# NTP_Clock_stm32f107.net
KiCad netlist of a schematic drawn in Altium Designer
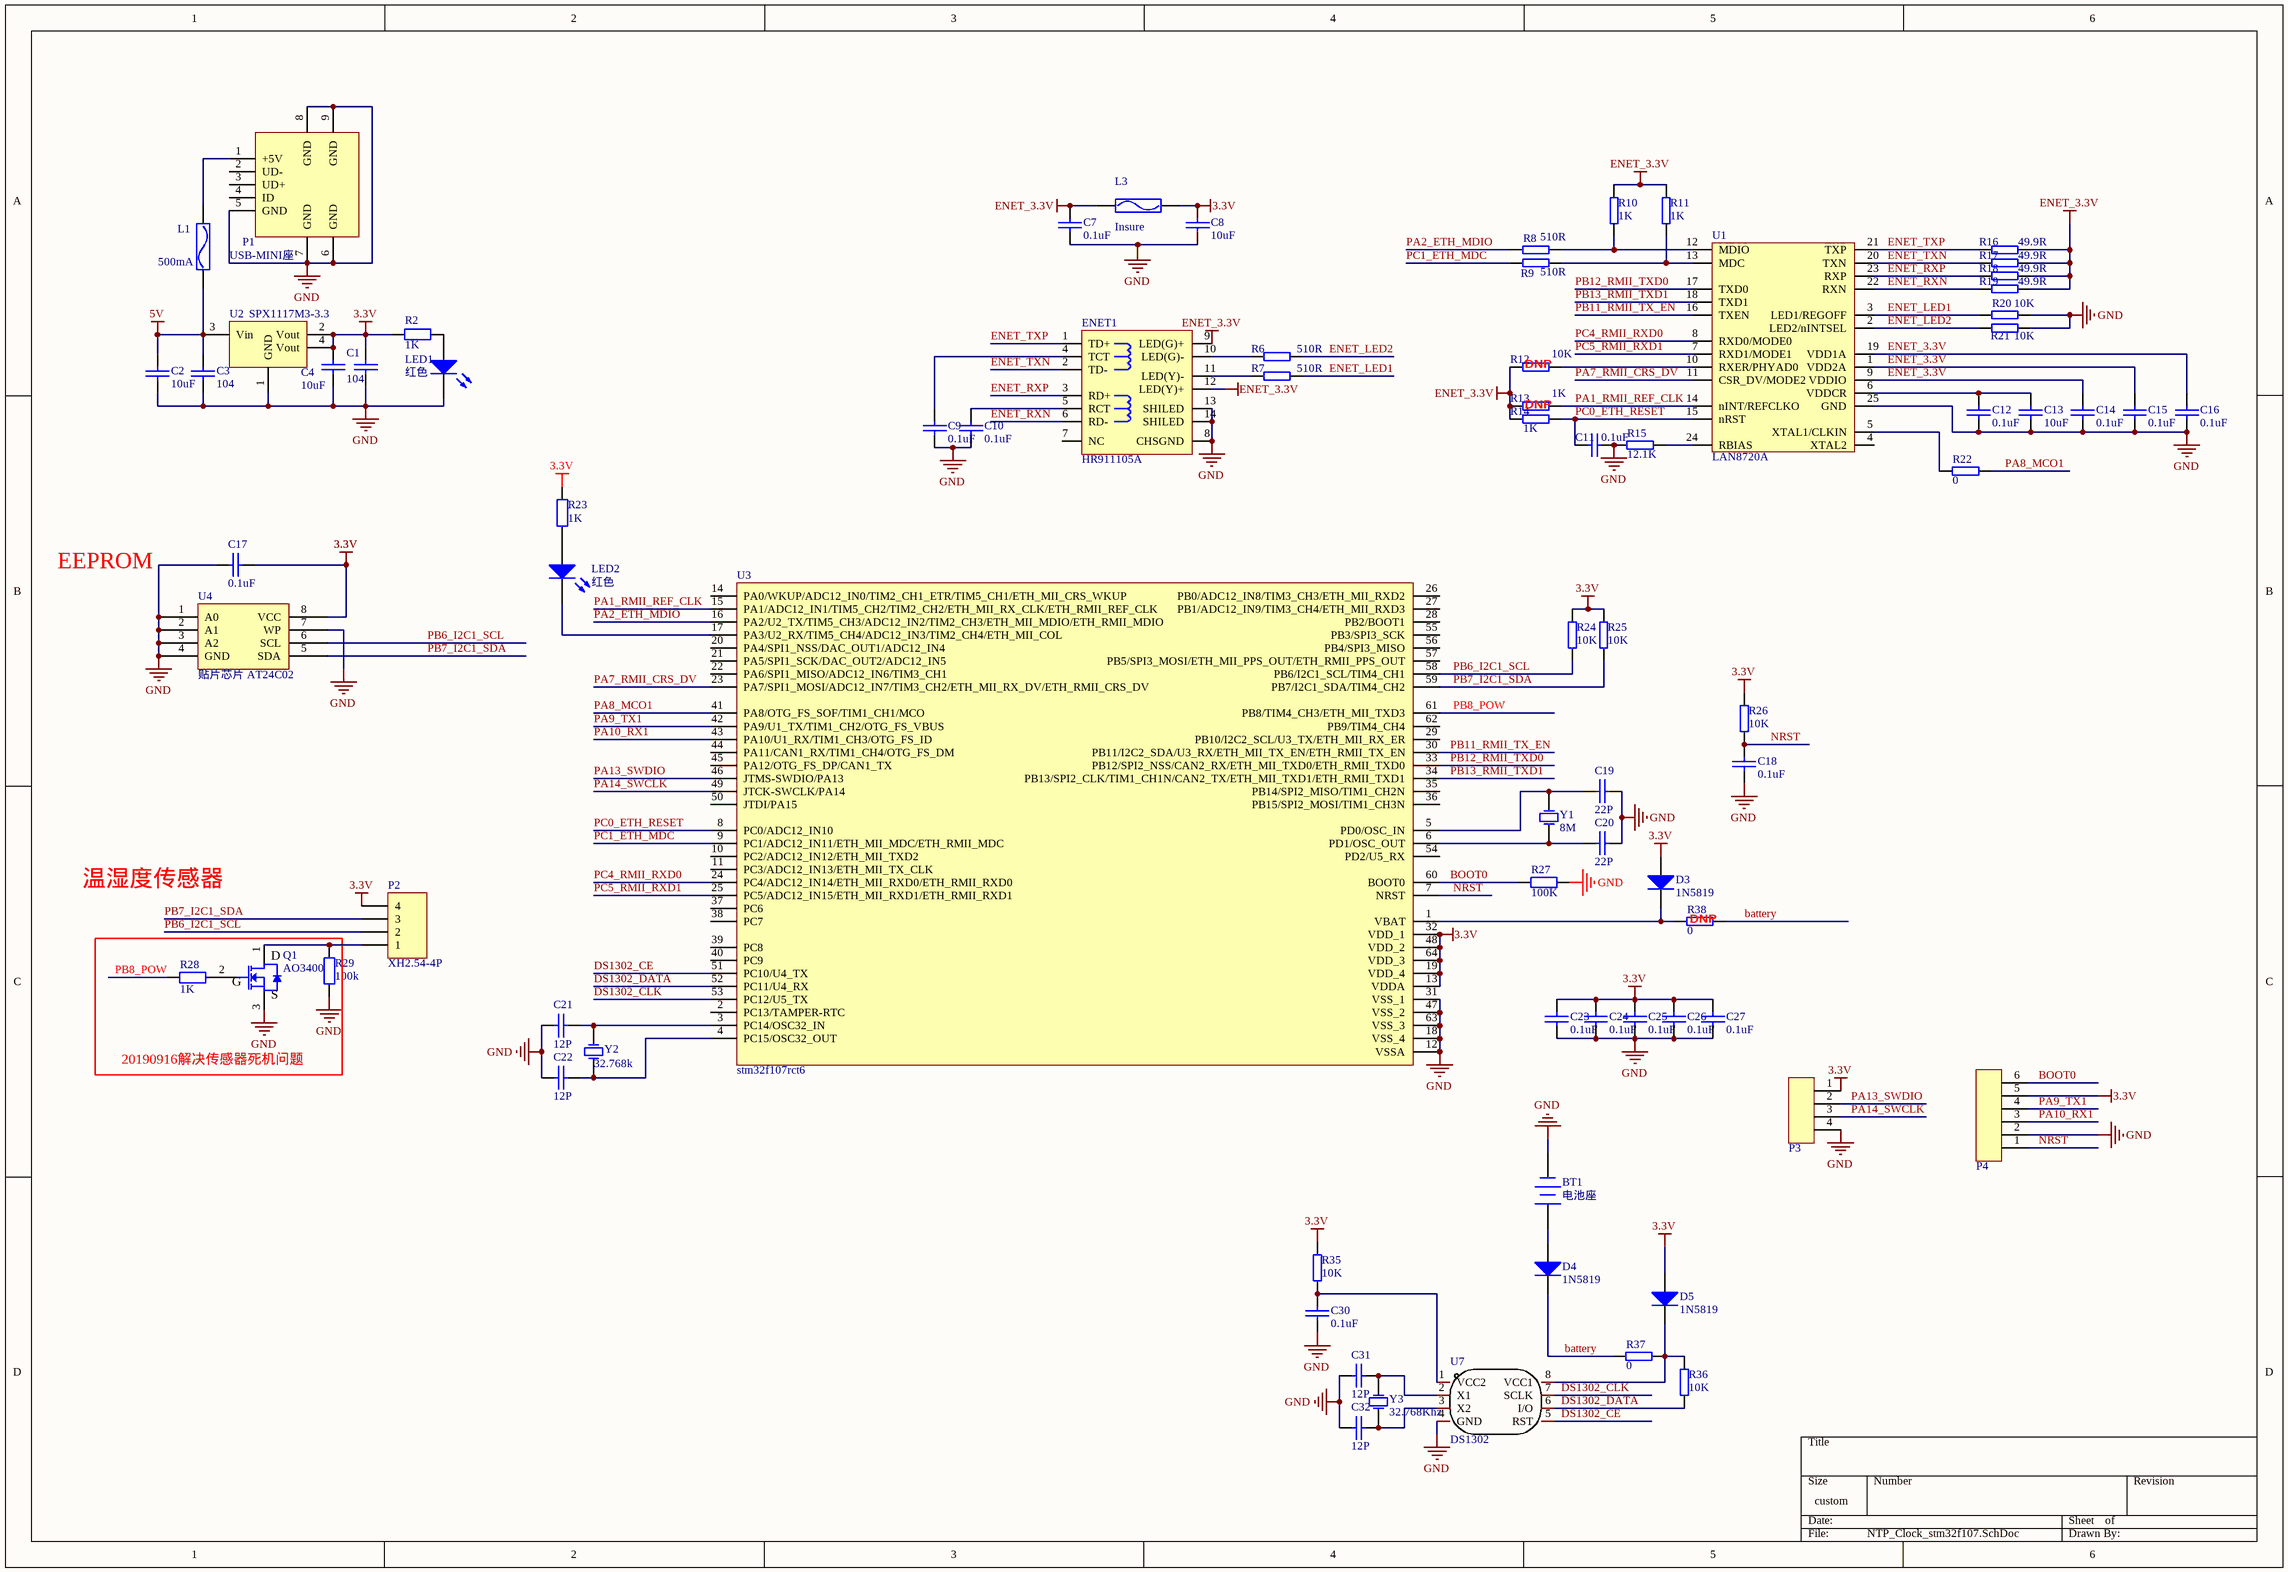
[diagram p0: NTP_Clock_stm32f107.SchDoc]

(export (version "E")
  (design (tool "Eeschema 10.0.6"))
  (components
    (comp (ref "BT1")
      (value "电池座")
      (footprint "BAT-3V")
      (fields (field (name "PUBLISHER") "Altium Limited"))
      (libsource (lib "Sch_Device_veryaz") (part "电池座"))
    )
    (comp (ref "C1")
      (value "104")
      (footprint "0805")
      (libsource (lib "Sch_Device_Simple") (part "贴片电容 0805"))
    )
    (comp (ref "C2")
      (value "10uF")
      (footprint "1206")
      (libsource (lib "Sch_Device_Simple") (part "贴片电容 0805"))
    )
    (comp (ref "C3")
      (value "104")
      (footprint "0805")
      (libsource (lib "Sch_Device_Simple") (part "贴片电容 0805"))
    )
    (comp (ref "C4")
      (value "10uF")
      (footprint "1206")
      (libsource (lib "Sch_Device_Simple") (part "贴片电容 0805"))
    )
    (comp (ref "C7") (value "0.1uF") (footprint "0805") (libsource (lib "Sch_Device_veryaz") (part "电容 贴片")))
    (comp (ref "C8") (value "10uF") (footprint "1206") (libsource (lib "Sch_Device_veryaz") (part "电容 贴片")))
    (comp (ref "C9") (value "0.1uF") (footprint "0805") (libsource (lib "Sch_Device_veryaz") (part "电容 贴片")))
    (comp (ref "C10") (value "0.1uF") (footprint "0805") (libsource (lib "Sch_Device_veryaz") (part "电容 贴片")))
    (comp (ref "C11") (value "0.1uF") (footprint "0805") (libsource (lib "Sch_Device_veryaz") (part "电容 贴片")))
    (comp (ref "C12") (value "0.1uF") (footprint "0805") (libsource (lib "Sch_Device_veryaz") (part "电容 贴片")))
    (comp (ref "C13") (value "10uF") (footprint "1206") (libsource (lib "Sch_Device_veryaz") (part "电容 贴片")))
    (comp (ref "C14") (value "0.1uF") (footprint "0805") (libsource (lib "Sch_Device_veryaz") (part "电容 贴片")))
    (comp (ref "C15") (value "0.1uF") (footprint "0805") (libsource (lib "Sch_Device_veryaz") (part "电容 贴片")))
    (comp (ref "C16") (value "0.1uF") (footprint "0805") (libsource (lib "Sch_Device_veryaz") (part "电容 贴片")))
    (comp (ref "C17") (value "0.1uF") (footprint "0805") (libsource (lib "Sch_Device_veryaz") (part "电容 贴片")))
    (comp (ref "C18") (value "0.1uF") (footprint "0805") (libsource (lib "Sch_Device_veryaz") (part "电容 贴片")))
    (comp (ref "C19") (value "22P") (footprint "0805") (libsource (lib "Sch_Device_veryaz") (part "电容 贴片")))
    (comp (ref "C20") (value "22P") (footprint "0805") (libsource (lib "Sch_Device_veryaz") (part "电容 贴片")))
    (comp (ref "C21") (value "12P") (footprint "0805") (libsource (lib "Sch_Device_veryaz") (part "电容 贴片")))
    (comp (ref "C22") (value "12P") (footprint "0805") (libsource (lib "Sch_Device_veryaz") (part "电容 贴片")))
    (comp (ref "C23") (value "0.1uF") (footprint "0805") (libsource (lib "Sch_Device_veryaz") (part "电容 贴片")))
    (comp (ref "C24") (value "0.1uF") (footprint "0805") (libsource (lib "Sch_Device_veryaz") (part "电容 贴片")))
    (comp (ref "C25") (value "0.1uF") (footprint "0805") (libsource (lib "Sch_Device_veryaz") (part "电容 贴片")))
    (comp (ref "C26") (value "0.1uF") (footprint "0805") (libsource (lib "Sch_Device_veryaz") (part "电容 贴片")))
    (comp (ref "C27") (value "0.1uF") (footprint "0805") (libsource (lib "Sch_Device_veryaz") (part "电容 贴片")))
    (comp (ref "C30") (value "0.1uF") (footprint "0805") (libsource (lib "Sch_Device_veryaz") (part "电容 贴片")))
    (comp (ref "C31") (value "12P") (footprint "0805") (libsource (lib "Sch_Device_veryaz") (part "电容 贴片")))
    (comp (ref "C32") (value "12P") (footprint "0805") (libsource (lib "Sch_Device_veryaz") (part "电容 贴片")))
    (comp (ref "D3")
      (value "1N5819")
      (footprint "二极管 贴片 IN4148")
      (libsource (lib "Sch_Device_veryaz") (part "二极管 贴片 1N4148"))
    )
    (comp (ref "D4")
      (value "1N5819")
      (footprint "二极管 贴片 IN4148")
      (libsource (lib "Sch_Device_veryaz") (part "二极管 贴片 1N4148"))
    )
    (comp (ref "D5")
      (value "1N5819")
      (footprint "二极管 贴片 IN4148")
      (libsource (lib "Sch_Device_veryaz") (part "二极管 贴片 1N4148"))
    )
    (comp (ref "ENET1")
      (value "HR911105A")
      (footprint "RJ-45A12")
      (description "带灯以太网接口")
      (fields (field (name "版权归属") "源创客"))
      (libsource (lib "IMX6UL_ALPHA(底板)_V2.0") (part "HR911105A"))
    )
    (comp (ref "L1") (value "500mA") (footprint "0805") (libsource (lib "Sch_Device_veryaz") (part "保险_自恢复")))
    (comp (ref "L3")
      (value "Insure")
      (footprint "0805")
      (libsource (lib "Sch_Device_veryaz") (part "保险 自恢复"))
    )
    (comp (ref "LED1")
      (value "红色")
      (footprint "LED5_单色")
      (description "D_RED_D")
      (libsource (lib "Sch_Device_Simple") (part "发光二极管 Φ3"))
    )
    (comp (ref "LED2")
      (value "红色")
      (footprint "LED5_单色")
      (description "D_RED_D")
      (libsource (lib "Sch_Device_Simple") (part "发光二极管 Φ3"))
    )
    (comp (ref "P1")
      (value "USB-MINI座")
      (footprint "USB MINI DIP")
      (libsource (lib "Sch_Device_veryaz") (part "联结件 USB-MINI座"))
    )
    (comp (ref "P2")
      (value "XH2.54-4P")
      (footprint "CONN-SMD_HCZZ0021-4")
      (libsource (lib "Sch_Device_veryaz") (part "联结件 XH2.54-4"))
    )
    (comp (ref "P3")
      (value "2.54 1*4")
      (footprint "单排插针 2.54 1*4")
      (libsource (lib "Sch_Device_veryaz") (part "连接件 单排插针 2.54 1*4"))
    )
    (comp (ref "P4")
      (value "2.54 1*6")
      (footprint "CONN-SMD_6P-P2.50_BX-HA2.54-6PWT")
      (libsource (lib "Sch_Device_veryaz") (part "连接件 单排插针 2.54 1*6"))
    )
    (comp (ref "Q1")
      (value "AO3400")
      (footprint "sot23d")
      (libsource (lib "Sch_Device_veryaz") (part "MOS管 AO3400"))
    )
    (comp (ref "R2") (value "1K") (footprint "0805") (libsource (lib "Sch_Device_Simple") (part "贴片电阻 0805")))
    (comp (ref "R6") (value "510R") (footprint "0805") (libsource (lib "") (part "电阻 贴片_1")))
    (comp (ref "R7") (value "510R") (footprint "0805") (libsource (lib "") (part "电阻 贴片_1")))
    (comp (ref "R8") (value "510R") (footprint "0805") (libsource (lib "") (part "电阻 贴片_1")))
    (comp (ref "R9") (value "510R") (footprint "0805") (libsource (lib "") (part "电阻 贴片_1")))
    (comp (ref "R10") (value "1K") (footprint "0805") (libsource (lib "Sch_Device_veryaz") (part "电阻 贴片")))
    (comp (ref "R11") (value "1K") (footprint "0805") (libsource (lib "Sch_Device_veryaz") (part "电阻 贴片")))
    (comp (ref "R12") (value "10K") (footprint "0805") (libsource (lib "") (part "电阻 贴片_1")))
    (comp (ref "R13") (value "1K") (footprint "0805") (libsource (lib "") (part "电阻 贴片_1")))
    (comp (ref "R14") (value "1K") (footprint "0805") (libsource (lib "") (part "电阻 贴片_1")))
    (comp (ref "R15") (value "12.1K") (footprint "0805") (libsource (lib "") (part "电阻 贴片_1")))
    (comp (ref "R16") (value "49.9R") (footprint "0805") (libsource (lib "") (part "电阻 贴片_1")))
    (comp (ref "R17") (value "49.9R") (footprint "0805") (libsource (lib "") (part "电阻 贴片_1")))
    (comp (ref "R18") (value "49.9R") (footprint "0805") (libsource (lib "") (part "电阻 贴片_1")))
    (comp (ref "R19") (value "49.9R") (footprint "0805") (libsource (lib "") (part "电阻 贴片_1")))
    (comp (ref "R20") (value "10K") (footprint "0805") (libsource (lib "") (part "电阻 贴片_1")))
    (comp (ref "R21") (value "10K") (footprint "0805") (libsource (lib "") (part "电阻 贴片_1")))
    (comp (ref "R22") (value "0") (footprint "0805") (libsource (lib "") (part "电阻 贴片_1")))
    (comp (ref "R23") (value "1K") (footprint "0805") (libsource (lib "") (part "贴片电阻 0805_1")))
    (comp (ref "R24") (value "10K") (footprint "0805") (libsource (lib "Sch_Device_veryaz") (part "电阻 贴片")))
    (comp (ref "R25") (value "10K") (footprint "0805") (libsource (lib "Sch_Device_veryaz") (part "电阻 贴片")))
    (comp (ref "R26") (value "10K") (footprint "0805") (libsource (lib "") (part "电阻 贴片_2")))
    (comp (ref "R27")
      (value "100K")
      (footprint "0805")
      (libsource (lib "Sch_Device_Simple") (part "贴片电阻 0805"))
    )
    (comp (ref "R28") (value "1K") (footprint "0805") (libsource (lib "") (part "贴片电阻 0603_1")))
    (comp (ref "R29")
      (value "100k")
      (footprint "0805")
      (libsource (lib "Sch_Device_veryaz") (part "贴片电阻 0603"))
    )
    (comp (ref "R35") (value "10K") (footprint "0805") (libsource (lib "") (part "电阻 贴片_2")))
    (comp (ref "R36") (value "10K") (footprint "0805") (libsource (lib "Sch_Device_veryaz") (part "电阻 贴片")))
    (comp (ref "R37") (value "0") (footprint "0805") (libsource (lib "") (part "电阻 贴片_1")))
    (comp (ref "R38") (value "0") (footprint "0805") (libsource (lib "") (part "电阻 贴片_1")))
    (comp (ref "U1")
      (value "LAN8720A")
      (footprint "QFN24")
      (description "ETH PHY")
      (libsource (lib "IMX6UL_ALPHA(底板)_V2.0") (part "LAN8720"))
    )
    (comp (ref "U2")
      (value "SPX1117M3-3.3")
      (footprint "SOT223")
      (libsource (lib "Sch_Device_veryaz") (part "贴片芯片 SPX1117M3-5.0"))
    )
    (comp (ref "U3")
      (value "stm32f107rct6")
      (footprint "stm32f107rct6")
      (libsource (lib "MyLib") (part "stm32f107rct6"))
    )
    (comp (ref "U4")
      (value "贴片芯片 AT24C02")
      (footprint "SOIC8")
      (libsource (lib "Sch_Device_veryaz") (part "贴片芯片 AT24C02"))
    )
    (comp (ref "U7")
      (value "DS1302")
      (footprint "SOP-8_L4.9-W3.9-P1.27-LS6.0-BL")
      (description "工业级 具有涓细电流充电能力的低功耗实时时钟芯片")
      (fields
        (field (name "MANUFACTURER") "HGSEMI(华冠)")
        (field (name "MANUFACTURER PART") "DS1302ZM")
        (field (name "NAME") "DS1302")
      )
      (libsource (lib "Sch_Device_veryaz") (part "DS1302"))
    )
    (comp (ref "Y1")
      (value "8M")
      (footprint "晶振 BCY-W2/E4.7_贴")
      (libsource (lib "Sch_Device_veryaz") (part "晶振 直插矮"))
    )
    (comp (ref "Y2") (value "32.768k") (footprint "晶振 卧 8*2mm") (libsource (lib "") (part "晶振 直插矮_1")))
    (comp (ref "Y3")
      (value "32.768Khz")
      (footprint "晶振 卧 8*2mm")
      (libsource (lib "Sch_Device_veryaz") (part "晶振 直插"))
    )
  )
  (nets
    (net (code "1") (name "/BOOT0") (class "Default")
      (node (ref "P4") (pin "6") (pinfunction "6_6") (pintype "passive"))
      (node (ref "R27") (pin "2") (pinfunction "2_2") (pintype "passive"))
      (node (ref "U3") (pin "60") (pinfunction "BOOT0_60") (pintype "passive"))
    )
    (net (code "2") (name "/DS1302_CE") (class "Default")
      (node (ref "U3") (pin "51") (pinfunction "PC10/U4_TX_51") (pintype "passive"))
      (node (ref "U7") (pin "5") (pinfunction "RST_5") (pintype "passive"))
    )
    (net (code "3") (name "/DS1302_CLK") (class "Default")
      (node (ref "U3") (pin "53") (pinfunction "PC12/U5_TX_53") (pintype "passive"))
      (node (ref "U7") (pin "7") (pinfunction "SCLK_7") (pintype "passive"))
    )
    (net (code "4") (name "/DS1302_DATA") (class "Default")
      (node (ref "R36") (pin "2") (pinfunction "2_2") (pintype "passive"))
      (node (ref "U3") (pin "52") (pinfunction "PC11/U4_RX_52") (pintype "passive"))
      (node (ref "U7") (pin "6") (pinfunction "I/O_6") (pintype "passive"))
    )
    (net (code "5") (name "/ENET_LED1") (class "Default")
      (node (ref "R20") (pin "2") (pinfunction "2_2") (pintype "passive"))
      (node (ref "R7") (pin "1") (pinfunction "1_1") (pintype "passive"))
      (node (ref "U1") (pin "3") (pinfunction "LED1/REGOFF_3") (pintype "passive"))
    )
    (net (code "6") (name "/ENET_LED2") (class "Default")
      (node (ref "R21") (pin "2") (pinfunction "2_2") (pintype "passive"))
      (node (ref "R6") (pin "1") (pinfunction "1_1") (pintype "passive"))
      (node (ref "U1") (pin "2") (pinfunction "LED2/nINTSEL_2") (pintype "passive"))
    )
    (net (code "7") (name "/ENET_RXN") (class "Default")
      (node (ref "ENET1") (pin "6") (pinfunction "RD-_6") (pintype "passive"))
      (node (ref "R19") (pin "2") (pinfunction "2_2") (pintype "passive"))
      (node (ref "U1") (pin "22") (pinfunction "RXN_22") (pintype "passive"))
    )
    (net (code "8") (name "/ENET_RXP") (class "Default")
      (node (ref "ENET1") (pin "3") (pinfunction "RD+_3") (pintype "passive"))
      (node (ref "R18") (pin "2") (pinfunction "2_2") (pintype "passive"))
      (node (ref "U1") (pin "23") (pinfunction "RXP_23") (pintype "passive"))
    )
    (net (code "9") (name "/ENET_TXN") (class "Default")
      (node (ref "ENET1") (pin "2") (pinfunction "TD-_2") (pintype "passive"))
      (node (ref "R17") (pin "2") (pinfunction "2_2") (pintype "passive"))
      (node (ref "U1") (pin "20") (pinfunction "TXN_20") (pintype "passive"))
    )
    (net (code "10") (name "/ENET_TXP") (class "Default")
      (node (ref "ENET1") (pin "1") (pinfunction "TD+_1") (pintype "passive"))
      (node (ref "R16") (pin "2") (pinfunction "2_2") (pintype "passive"))
      (node (ref "U1") (pin "21") (pinfunction "TXP_21") (pintype "passive"))
    )
    (net (code "11") (name "/NRST") (class "Default")
      (node (ref "C18") (pin "1") (pintype "passive"))
      (node (ref "P4") (pin "1") (pinfunction "1_1") (pintype "passive"))
      (node (ref "R26") (pin "1") (pinfunction "1_1") (pintype "passive"))
      (node (ref "U3") (pin "7") (pinfunction "NRST_7") (pintype "passive"))
    )
    (net (code "12") (name "/PA1_RMII_REF_CLK") (class "Default")
      (node (ref "R13") (pin "1") (pinfunction "1_1") (pintype "passive"))
      (node (ref "U1") (pin "14") (pinfunction "nINT/REFCLKO_14") (pintype "passive"))
      (node (ref "U3") (pin "15") (pinfunction "PA1/ADC12_IN1/TIM5_CH2/TIM2_CH2/ETH_MII_RX_CLK/ETH_RMII_REF_CLK_15") (pintype "passive"))
    )
    (net (code "13") (name "/PA2_ETH_MDIO") (class "Default")
      (node (ref "R8") (pin "2") (pinfunction "2_2") (pintype "passive"))
      (node (ref "U3") (pin "16") (pinfunction "PA2/U2_TX/TIM5_CH3/ADC12_IN2/TIM2_CH3/ETH_MII_MDIO/ETH_RMII_MDIO_16") (pintype "passive"))
    )
    (net (code "14") (name "/PA7_RMII_CRS_DV") (class "Default")
      (node (ref "U1") (pin "11") (pinfunction "CSR_DV/MODE2_11") (pintype "passive"))
      (node (ref "U3") (pin "23") (pinfunction "PA7/SPI1_MOSI/ADC12_IN7/TIM3_CH2/ETH_MII_RX_DV/ETH_RMII_CRS_DV_23") (pintype "passive"))
    )
    (net (code "15") (name "/PA8_MCO1") (class "Default")
      (node (ref "R22") (pin "1") (pinfunction "1_1") (pintype "passive"))
      (node (ref "U3") (pin "41") (pinfunction "PA8/OTG_FS_SOF/TIM1_CH1/MCO_41") (pintype "passive"))
    )
    (net (code "16") (name "/PA9_TX1") (class "Default")
      (node (ref "P4") (pin "4") (pinfunction "4_4") (pintype "passive"))
      (node (ref "U3") (pin "42") (pinfunction "PA9/U1_TX/TIM1_CH2/OTG_FS_VBUS_42") (pintype "passive"))
    )
    (net (code "17") (name "/PA10_RX1") (class "Default")
      (node (ref "P4") (pin "3") (pinfunction "3_3") (pintype "passive"))
      (node (ref "U3") (pin "43") (pinfunction "PA10/U1_RX/TIM1_CH3/OTG_FS_ID_43") (pintype "passive"))
    )
    (net (code "18") (name "/PA13_SWDIO") (class "Default")
      (node (ref "P3") (pin "2") (pinfunction "2_2") (pintype "passive"))
      (node (ref "U3") (pin "46") (pinfunction "JTMS-SWDIO/PA13_46") (pintype "passive"))
    )
    (net (code "19") (name "/PA14_SWCLK") (class "Default")
      (node (ref "P3") (pin "3") (pinfunction "3_3") (pintype "passive"))
      (node (ref "U3") (pin "49") (pinfunction "JTCK-SWCLK/PA14_49") (pintype "passive"))
    )
    (net (code "20") (name "/PB6_I2C1_SCL") (class "Default")
      (node (ref "P2") (pin "2") (pinfunction "2_2") (pintype "passive"))
      (node (ref "R24") (pin "2") (pinfunction "2_2") (pintype "passive"))
      (node (ref "U3") (pin "58") (pinfunction "PB6/I2C1_SCL/TIM4_CH1_58") (pintype "passive"))
      (node (ref "U4") (pin "6") (pinfunction "SCL_6") (pintype "passive"))
    )
    (net (code "21") (name "/PB7_I2C1_SDA") (class "Default")
      (node (ref "P2") (pin "3") (pinfunction "3_3") (pintype "passive"))
      (node (ref "R25") (pin "2") (pinfunction "2_2") (pintype "passive"))
      (node (ref "U3") (pin "59") (pinfunction "PB7/I2C1_SDA/TIM4_CH2_59") (pintype "passive"))
      (node (ref "U4") (pin "5") (pinfunction "SDA_5") (pintype "passive"))
    )
    (net (code "22") (name "/PB8_POW") (class "Default")
      (node (ref "R28") (pin "2") (pinfunction "2_2") (pintype "passive"))
      (node (ref "U3") (pin "61") (pinfunction "PB8/TIM4_CH3/ETH_MII_TXD3_61") (pintype "passive"))
    )
    (net (code "23") (name "/PB11_RMII_TX_EN") (class "Default")
      (node (ref "U1") (pin "16") (pinfunction "TXEN_16") (pintype "passive"))
      (node (ref "U3") (pin "30") (pinfunction "PB11/I2C2_SDA/U3_RX/ETH_MII_TX_EN/ETH_RMII_TX_EN_30") (pintype "passive"))
    )
    (net (code "24") (name "/PB12_RMII_TXD0") (class "Default")
      (node (ref "U1") (pin "17") (pinfunction "TXD0_17") (pintype "passive"))
      (node (ref "U3") (pin "33") (pinfunction "PB12/SPI2_NSS/CAN2_RX/ETH_MII_TXD0/ETH_RMII_TXD0_33") (pintype "passive"))
    )
    (net (code "25") (name "/PB13_RMII_TXD1") (class "Default")
      (node (ref "U1") (pin "18") (pinfunction "TXD1_18") (pintype "passive"))
      (node (ref "U3") (pin "34") (pinfunction "PB13/SPI2_CLK/TIM1_CH1N/CAN2_TX/ETH_MII_TXD1/ETH_RMII_TXD1_34") (pintype "passive"))
    )
    (net (code "26") (name "/PC0_ETH_RESET") (class "Default")
      (node (ref "C11") (pin "1") (pintype "passive"))
      (node (ref "R14") (pin "1") (pinfunction "1_1") (pintype "passive"))
      (node (ref "U1") (pin "15") (pinfunction "nRST_15") (pintype "passive"))
      (node (ref "U3") (pin "8") (pinfunction "PC0/ADC12_IN10_8") (pintype "passive"))
    )
    (net (code "27") (name "/PC1_ETH_MDC") (class "Default")
      (node (ref "R9") (pin "2") (pinfunction "2_2") (pintype "passive"))
      (node (ref "U3") (pin "9") (pinfunction "PC1/ADC12_IN11/ETH_MII_MDC/ETH_RMII_MDC_9") (pintype "passive"))
    )
    (net (code "28") (name "/PC4_RMII_RXD0") (class "Default")
      (node (ref "U1") (pin "8") (pinfunction "RXD0/MODE0_8") (pintype "passive"))
      (node (ref "U3") (pin "24") (pinfunction "PC4/ADC12_IN14/ETH_MII_RXD0/ETH_RMII_RXD0_24") (pintype "passive"))
    )
    (net (code "29") (name "/PC5_RMII_RXD1") (class "Default")
      (node (ref "U1") (pin "7") (pinfunction "RXD1/MODE1_7") (pintype "passive"))
      (node (ref "U3") (pin "25") (pinfunction "PC5/ADC12_IN15/ETH_MII_RXD1/ETH_RMII_RXD1_25") (pintype "passive"))
    )
    (net (code "30") (name "/battery") (class "Default")
      (node (ref "D4") (pin "2") (pinfunction "K_2") (pintype "passive"))
      (node (ref "R37") (pin "2") (pinfunction "2_2") (pintype "passive"))
      (node (ref "R38") (pin "1") (pinfunction "1_1") (pintype "passive"))
    )
    (net (code "31") (name "3.3V") (class "Default")
      (node (ref "C1") (pin "1") (pintype "passive"))
      (node (ref "C17") (pin "1") (pintype "passive"))
      (node (ref "C23") (pin "2") (pintype "passive"))
      (node (ref "C24") (pin "2") (pintype "passive"))
      (node (ref "C25") (pin "2") (pintype "passive"))
      (node (ref "C26") (pin "2") (pintype "passive"))
      (node (ref "C27") (pin "2") (pintype "passive"))
      (node (ref "C4") (pin "1") (pintype "passive"))
      (node (ref "C8") (pin "2") (pintype "passive"))
      (node (ref "D3") (pin "1") (pinfunction "A_1") (pintype "passive"))
      (node (ref "D5") (pin "1") (pinfunction "A_1") (pintype "passive"))
      (node (ref "L3") (pin "2") (pinfunction "2_2") (pintype "passive"))
      (node (ref "P2") (pin "4") (pinfunction "4_4") (pintype "passive"))
      (node (ref "P3") (pin "1") (pinfunction "1_1") (pintype "passive"))
      (node (ref "P4") (pin "5") (pinfunction "5_5") (pintype "passive"))
      (node (ref "R2") (pin "2") (pinfunction "2_2") (pintype "passive"))
      (node (ref "R23") (pin "1") (pinfunction "1_1") (pintype "passive"))
      (node (ref "R24") (pin "1") (pinfunction "1_1") (pintype "passive"))
      (node (ref "R25") (pin "1") (pinfunction "1_1") (pintype "passive"))
      (node (ref "R26") (pin "2") (pinfunction "2_2") (pintype "passive"))
      (node (ref "R35") (pin "2") (pinfunction "2_2") (pintype "passive"))
      (node (ref "U2") (pin "2") (pinfunction "Vout_2") (pintype "passive"))
      (node (ref "U2") (pin "4") (pinfunction "Vout_4") (pintype "passive"))
      (node (ref "U3") (pin "13") (pinfunction "VDDA_13") (pintype "passive"))
      (node (ref "U3") (pin "19") (pinfunction "VDD_4_19") (pintype "passive"))
      (node (ref "U3") (pin "32") (pinfunction "VDD_1_32") (pintype "passive"))
      (node (ref "U3") (pin "48") (pinfunction "VDD_2_48") (pintype "passive"))
      (node (ref "U3") (pin "64") (pinfunction "VDD_3_64") (pintype "passive"))
      (node (ref "U4") (pin "8") (pinfunction "VCC_8") (pintype "passive"))
    )
    (net (code "32") (name "5V") (class "Default")
      (node (ref "C2") (pin "1") (pintype "passive"))
      (node (ref "C3") (pin "1") (pintype "passive"))
      (node (ref "L1") (pin "1") (pinfunction "1_1") (pintype "passive"))
      (node (ref "U2") (pin "3") (pinfunction "Vin_3") (pintype "passive"))
    )
    (net (code "33") (name "ENET_3.3V") (class "Default")
      (node (ref "C14") (pin "2") (pintype "passive"))
      (node (ref "C15") (pin "2") (pintype "passive"))
      (node (ref "C16") (pin "2") (pintype "passive"))
      (node (ref "C7") (pin "2") (pintype "passive"))
      (node (ref "ENET1") (pin "12") (pinfunction "LED(Y)+_12") (pintype "passive"))
      (node (ref "ENET1") (pin "9") (pinfunction "LED(G)+_9") (pintype "passive"))
      (node (ref "L3") (pin "1") (pinfunction "1_1") (pintype "passive"))
      (node (ref "R10") (pin "1") (pinfunction "1_1") (pintype "passive"))
      (node (ref "R11") (pin "1") (pinfunction "1_1") (pintype "passive"))
      (node (ref "R12") (pin "2") (pinfunction "2_2") (pintype "passive"))
      (node (ref "R13") (pin "2") (pinfunction "2_2") (pintype "passive"))
      (node (ref "R14") (pin "2") (pinfunction "2_2") (pintype "passive"))
      (node (ref "R16") (pin "1") (pinfunction "1_1") (pintype "passive"))
      (node (ref "R17") (pin "1") (pinfunction "1_1") (pintype "passive"))
      (node (ref "R18") (pin "1") (pinfunction "1_1") (pintype "passive"))
      (node (ref "R19") (pin "1") (pinfunction "1_1") (pintype "passive"))
      (node (ref "U1") (pin "1") (pinfunction "VDD2A_1") (pintype "passive"))
      (node (ref "U1") (pin "19") (pinfunction "VDD1A_19") (pintype "passive"))
      (node (ref "U1") (pin "9") (pinfunction "VDDIO_9") (pintype "passive"))
    )
    (net (code "34") (name "GND") (class "Default")
      (node (ref "BT1") (pin "2") (pinfunction "-_2") (pintype "passive"))
      (node (ref "C1") (pin "2") (pintype "passive"))
      (node (ref "C10") (pin "1") (pintype "passive"))
      (node (ref "C11") (pin "2") (pintype "passive"))
      (node (ref "C12") (pin "1") (pintype "passive"))
      (node (ref "C13") (pin "1") (pintype "passive"))
      (node (ref "C14") (pin "1") (pintype "passive"))
      (node (ref "C15") (pin "1") (pintype "passive"))
      (node (ref "C16") (pin "1") (pintype "passive"))
      (node (ref "C17") (pin "2") (pintype "passive"))
      (node (ref "C18") (pin "2") (pintype "passive"))
      (node (ref "C19") (pin "2") (pintype "passive"))
      (node (ref "C2") (pin "2") (pintype "passive"))
      (node (ref "C20") (pin "2") (pintype "passive"))
      (node (ref "C21") (pin "1") (pintype "passive"))
      (node (ref "C22") (pin "1") (pintype "passive"))
      (node (ref "C23") (pin "1") (pintype "passive"))
      (node (ref "C24") (pin "1") (pintype "passive"))
      (node (ref "C25") (pin "1") (pintype "passive"))
      (node (ref "C26") (pin "1") (pintype "passive"))
      (node (ref "C27") (pin "1") (pintype "passive"))
      (node (ref "C3") (pin "2") (pintype "passive"))
      (node (ref "C30") (pin "2") (pintype "passive"))
      (node (ref "C31") (pin "1") (pintype "passive"))
      (node (ref "C32") (pin "1") (pintype "passive"))
      (node (ref "C4") (pin "2") (pintype "passive"))
      (node (ref "C7") (pin "1") (pintype "passive"))
      (node (ref "C8") (pin "1") (pintype "passive"))
      (node (ref "C9") (pin "1") (pintype "passive"))
      (node (ref "ENET1") (pin "13") (pinfunction "SHILED_13") (pintype "passive"))
      (node (ref "ENET1") (pin "14") (pinfunction "SHILED_14") (pintype "passive"))
      (node (ref "ENET1") (pin "8") (pinfunction "CHSGND_8") (pintype "passive"))
      (node (ref "LED1") (pin "2") (pinfunction "K_2") (pintype "passive"))
      (node (ref "P1") (pin "5") (pinfunction "GND_5") (pintype "passive"))
      (node (ref "P1") (pin "6") (pinfunction "GND_6") (pintype "passive"))
      (node (ref "P1") (pin "7") (pinfunction "GND_7") (pintype "passive"))
      (node (ref "P1") (pin "8") (pinfunction "GND_8") (pintype "passive"))
      (node (ref "P1") (pin "9") (pinfunction "GND_9") (pintype "passive"))
      (node (ref "P3") (pin "4") (pinfunction "4_4") (pintype "passive"))
      (node (ref "P4") (pin "2") (pinfunction "2_2") (pintype "passive"))
      (node (ref "Q1") (pin "3") (pinfunction "S_3") (pintype "passive"))
      (node (ref "R15") (pin "2") (pinfunction "2_2") (pintype "passive"))
      (node (ref "R20") (pin "1") (pinfunction "1_1") (pintype "passive"))
      (node (ref "R21") (pin "1") (pinfunction "1_1") (pintype "passive"))
      (node (ref "R27") (pin "1") (pinfunction "1_1") (pintype "passive"))
      (node (ref "R29") (pin "2") (pinfunction "2_2") (pintype "passive"))
      (node (ref "U1") (pin "25") (pinfunction "GND_25") (pintype "passive"))
      (node (ref "U2") (pin "1") (pinfunction "GND_1") (pintype "passive"))
      (node (ref "U3") (pin "12") (pinfunction "VSSA_12") (pintype "passive"))
      (node (ref "U3") (pin "18") (pinfunction "VSS_4_18") (pintype "passive"))
      (node (ref "U3") (pin "31") (pinfunction "VSS_1_31") (pintype "passive"))
      (node (ref "U3") (pin "47") (pinfunction "VSS_2_47") (pintype "passive"))
      (node (ref "U3") (pin "63") (pinfunction "VSS_3_63") (pintype "passive"))
      (node (ref "U4") (pin "1") (pinfunction "A0_1") (pintype "passive"))
      (node (ref "U4") (pin "2") (pinfunction "A1_2") (pintype "passive"))
      (node (ref "U4") (pin "3") (pinfunction "A2_3") (pintype "passive"))
      (node (ref "U4") (pin "4") (pinfunction "GND_4") (pintype "passive"))
      (node (ref "U4") (pin "7") (pinfunction "WP_7") (pintype "passive"))
      (node (ref "U7") (pin "4") (pinfunction "GND_4") (pintype "passive"))
    )
    (net (code "35") (name "Net-(BT1-+)") (class "Default")
      (node (ref "BT1") (pin "1") (pinfunction "+_1") (pintype "passive"))
      (node (ref "D4") (pin "1") (pinfunction "A_1") (pintype "passive"))
    )
    (net (code "36") (name "Net-(D3-K)") (class "Default")
      (node (ref "D3") (pin "2") (pinfunction "K_2") (pintype "passive"))
      (node (ref "R38") (pin "2") (pinfunction "2_2") (pintype "passive"))
      (node (ref "U3") (pin "1") (pinfunction "VBAT_1") (pintype "passive"))
    )
    (net (code "37") (name "Net-(D5-K)") (class "Default")
      (node (ref "D5") (pin "2") (pinfunction "K_2") (pintype "passive"))
      (node (ref "R36") (pin "1") (pinfunction "1_1") (pintype "passive"))
      (node (ref "R37") (pin "1") (pinfunction "1_1") (pintype "passive"))
      (node (ref "U7") (pin "8") (pinfunction "VCC1_8") (pintype "passive"))
    )
    (net (code "38") (name "Net-(ENET1-LED(G)-)") (class "Default")
      (node (ref "ENET1") (pin "10") (pinfunction "LED(G)-_10") (pintype "passive"))
      (node (ref "R6") (pin "2") (pinfunction "2_2") (pintype "passive"))
    )
    (net (code "39") (name "Net-(ENET1-LED(Y)-)") (class "Default")
      (node (ref "ENET1") (pin "11") (pinfunction "LED(Y)-_11") (pintype "passive"))
      (node (ref "R7") (pin "2") (pinfunction "2_2") (pintype "passive"))
    )
    (net (code "40") (name "Net-(ENET1-RCT)") (class "Default")
      (node (ref "C10") (pin "2") (pintype "passive"))
      (node (ref "ENET1") (pin "5") (pinfunction "RCT_5") (pintype "passive"))
    )
    (net (code "41") (name "Net-(ENET1-TCT)") (class "Default")
      (node (ref "C9") (pin "2") (pintype "passive"))
      (node (ref "ENET1") (pin "4") (pinfunction "TCT_4") (pintype "passive"))
    )
    (net (code "42") (name "Net-(LED1-A)") (class "Default")
      (node (ref "LED1") (pin "1") (pinfunction "A_1") (pintype "passive"))
      (node (ref "R2") (pin "1") (pinfunction "1_1") (pintype "passive"))
    )
    (net (code "43") (name "Net-(LED2-A)") (class "Default")
      (node (ref "LED2") (pin "1") (pinfunction "A_1") (pintype "passive"))
      (node (ref "R23") (pin "2") (pinfunction "2_2") (pintype "passive"))
    )
    (net (code "44") (name "Net-(LED2-K)") (class "Default")
      (node (ref "LED2") (pin "2") (pinfunction "K_2") (pintype "passive"))
      (node (ref "U3") (pin "17") (pinfunction "PA3/U2_RX/TIM5_CH4/ADC12_IN3/TIM2_CH4/ETH_MII_COL_17") (pintype "passive"))
    )
    (net (code "45") (name "Net-(P1-+5V)") (class "Default")
      (node (ref "L1") (pin "2") (pinfunction "2_2") (pintype "passive"))
      (node (ref "P1") (pin "1") (pinfunction "+5V_1") (pintype "passive"))
    )
    (net (code "46") (name "Net-(Q1-D)") (class "Default")
      (node (ref "P2") (pin "1") (pinfunction "1_1") (pintype "passive"))
      (node (ref "Q1") (pin "1") (pinfunction "D_1") (pintype "passive"))
      (node (ref "R29") (pin "1") (pinfunction "1_1") (pintype "passive"))
    )
    (net (code "47") (name "Net-(Q1-G)") (class "Default")
      (node (ref "Q1") (pin "2") (pinfunction "G_2") (pintype "passive"))
      (node (ref "R28") (pin "1") (pinfunction "1_1") (pintype "passive"))
    )
    (net (code "48") (name "Net-(U1-MDC)") (class "Default")
      (node (ref "R11") (pin "2") (pinfunction "2_2") (pintype "passive"))
      (node (ref "R9") (pin "1") (pinfunction "1_1") (pintype "passive"))
      (node (ref "U1") (pin "13") (pinfunction "MDC_13") (pintype "passive"))
    )
    (net (code "49") (name "Net-(U1-MDIO)") (class "Default")
      (node (ref "R10") (pin "2") (pinfunction "2_2") (pintype "passive"))
      (node (ref "R8") (pin "1") (pinfunction "1_1") (pintype "passive"))
      (node (ref "U1") (pin "12") (pinfunction "MDIO_12") (pintype "passive"))
    )
    (net (code "50") (name "Net-(U1-RBIAS)") (class "Default")
      (node (ref "R15") (pin "1") (pinfunction "1_1") (pintype "passive"))
      (node (ref "U1") (pin "24") (pinfunction "RBIAS_24") (pintype "passive"))
    )
    (net (code "51") (name "Net-(U1-RXER{slash}PHYAD0)") (class "Default")
      (node (ref "R12") (pin "1") (pinfunction "1_1") (pintype "passive"))
      (node (ref "U1") (pin "10") (pinfunction "RXER/PHYAD0_10") (pintype "passive"))
    )
    (net (code "52") (name "Net-(U1-VDDCR)") (class "Default")
      (node (ref "C12") (pin "2") (pintype "passive"))
      (node (ref "C13") (pin "2") (pintype "passive"))
      (node (ref "U1") (pin "6") (pinfunction "VDDCR_6") (pintype "passive"))
    )
    (net (code "53") (name "Net-(U1-XTAL1{slash}CLKIN)") (class "Default")
      (node (ref "R22") (pin "2") (pinfunction "2_2") (pintype "passive"))
      (node (ref "U1") (pin "5") (pinfunction "XTAL1/CLKIN_5") (pintype "passive"))
    )
    (net (code "54") (name "Net-(U3-PC14{slash}OSC32_IN)") (class "Default")
      (node (ref "C21") (pin "2") (pintype "passive"))
      (node (ref "U3") (pin "3") (pinfunction "PC14/OSC32_IN_3") (pintype "passive"))
      (node (ref "Y2") (pin "1") (pinfunction "OSC1_1") (pintype "passive"))
    )
    (net (code "55") (name "Net-(U3-PC15{slash}OSC32_OUT)") (class "Default")
      (node (ref "C22") (pin "2") (pintype "passive"))
      (node (ref "U3") (pin "4") (pinfunction "PC15/OSC32_OUT_4") (pintype "passive"))
      (node (ref "Y2") (pin "2") (pinfunction "OSC2_2") (pintype "passive"))
    )
    (net (code "56") (name "Net-(U3-PD0{slash}OSC_IN)") (class "Default")
      (node (ref "C19") (pin "1") (pintype "passive"))
      (node (ref "U3") (pin "5") (pinfunction "PD0/OSC_IN_5") (pintype "passive"))
      (node (ref "Y1") (pin "2") (pinfunction "OSC2_2") (pintype "passive"))
    )
    (net (code "57") (name "Net-(U3-PD1{slash}OSC_OUT)") (class "Default")
      (node (ref "C20") (pin "1") (pintype "passive"))
      (node (ref "U3") (pin "6") (pinfunction "PD1/OSC_OUT_6") (pintype "passive"))
      (node (ref "Y1") (pin "1") (pinfunction "OSC1_1") (pintype "passive"))
    )
    (net (code "58") (name "Net-(U7-VCC2)") (class "Default")
      (node (ref "C30") (pin "1") (pintype "passive"))
      (node (ref "R35") (pin "1") (pinfunction "1_1") (pintype "passive"))
      (node (ref "U7") (pin "1") (pinfunction "VCC2_1") (pintype "passive"))
    )
    (net (code "59") (name "Net-(U7-X1)") (class "Default")
      (node (ref "C31") (pin "2") (pintype "passive"))
      (node (ref "U7") (pin "2") (pinfunction "X1_2") (pintype "passive"))
      (node (ref "Y3") (pin "1") (pinfunction "OSC1_1") (pintype "passive"))
    )
    (net (code "60") (name "Net-(U7-X2)") (class "Default")
      (node (ref "C32") (pin "2") (pintype "passive"))
      (node (ref "U7") (pin "3") (pinfunction "X2_3") (pintype "passive"))
      (node (ref "Y3") (pin "2") (pinfunction "OSC2_2") (pintype "passive"))
    )
    (net (code "61") (name "unconnected-(ENET1-NC-Pad7)") (class "Default")
      (node (ref "ENET1") (pin "7") (pinfunction "NC_7") (pintype "passive"))
    )
    (net (code "62") (name "unconnected-(P1-ID-Pad4)") (class "Default")
      (node (ref "P1") (pin "4") (pinfunction "ID_4") (pintype "passive"))
    )
    (net (code "63") (name "unconnected-(P1-UD+-Pad3)") (class "Default")
      (node (ref "P1") (pin "3") (pinfunction "UD+_3") (pintype "passive"))
    )
    (net (code "64") (name "unconnected-(P1-UD--Pad2)") (class "Default")
      (node (ref "P1") (pin "2") (pinfunction "UD-_2") (pintype "passive"))
    )
    (net (code "65") (name "unconnected-(U1-XTAL2-Pad4)") (class "Default")
      (node (ref "U1") (pin "4") (pinfunction "XTAL2_4") (pintype "passive"))
    )
    (net (code "66") (name "unconnected-(U3-JTDI{slash}PA15-Pad50)") (class "Default")
      (node (ref "U3") (pin "50") (pinfunction "JTDI/PA15_50") (pintype "passive"))
    )
    (net (code "67") (name "unconnected-(U3-PA0{slash}WKUP{slash}ADC12_IN0{slash}TIM2_CH1_ETR{slash}TIM5_CH1{slash}ETH_MII_CRS_WKUP-Pad14)") (class "Default")
      (node (ref "U3") (pin "14") (pinfunction "PA0/WKUP/ADC12_IN0/TIM2_CH1_ETR/TIM5_CH1/ETH_MII_CRS_WKUP_14") (pintype "passive"))
    )
    (net (code "68") (name "unconnected-(U3-PA4{slash}SPI1_NSS{slash}DAC_OUT1{slash}ADC12_IN4-Pad20)") (class "Default")
      (node (ref "U3") (pin "20") (pinfunction "PA4/SPI1_NSS/DAC_OUT1/ADC12_IN4_20") (pintype "passive"))
    )
    (net (code "69") (name "unconnected-(U3-PA5{slash}SPI1_SCK{slash}DAC_OUT2{slash}ADC12_IN5-Pad21)") (class "Default")
      (node (ref "U3") (pin "21") (pinfunction "PA5/SPI1_SCK/DAC_OUT2/ADC12_IN5_21") (pintype "passive"))
    )
    (net (code "70") (name "unconnected-(U3-PA6{slash}SPI1_MISO{slash}ADC12_IN6{slash}TIM3_CH1-Pad22)") (class "Default")
      (node (ref "U3") (pin "22") (pinfunction "PA6/SPI1_MISO/ADC12_IN6/TIM3_CH1_22") (pintype "passive"))
    )
    (net (code "71") (name "unconnected-(U3-PA11{slash}CAN1_RX{slash}TIM1_CH4{slash}OTG_FS_DM-Pad44)") (class "Default")
      (node (ref "U3") (pin "44") (pinfunction "PA11/CAN1_RX/TIM1_CH4/OTG_FS_DM_44") (pintype "passive"))
    )
    (net (code "72") (name "unconnected-(U3-PA12{slash}OTG_FS_DP{slash}CAN1_TX-Pad45)") (class "Default")
      (node (ref "U3") (pin "45") (pinfunction "PA12/OTG_FS_DP/CAN1_TX_45") (pintype "passive"))
    )
    (net (code "73") (name "unconnected-(U3-PB0{slash}ADC12_IN8{slash}TIM3_CH3{slash}ETH_MII_RXD2-Pad26)") (class "Default")
      (node (ref "U3") (pin "26") (pinfunction "PB0/ADC12_IN8/TIM3_CH3/ETH_MII_RXD2_26") (pintype "passive"))
    )
    (net (code "74") (name "unconnected-(U3-PB1{slash}ADC12_IN9{slash}TIM3_CH4{slash}ETH_MII_RXD3-Pad27)") (class "Default")
      (node (ref "U3") (pin "27") (pinfunction "PB1/ADC12_IN9/TIM3_CH4/ETH_MII_RXD3_27") (pintype "passive"))
    )
    (net (code "75") (name "unconnected-(U3-PB2{slash}BOOT1-Pad28)") (class "Default")
      (node (ref "U3") (pin "28") (pinfunction "PB2/BOOT1_28") (pintype "passive"))
    )
    (net (code "76") (name "unconnected-(U3-PB3{slash}SPI3_SCK-Pad55)") (class "Default")
      (node (ref "U3") (pin "55") (pinfunction "PB3/SPI3_SCK_55") (pintype "passive"))
    )
    (net (code "77") (name "unconnected-(U3-PB4{slash}SPI3_MISO-Pad56)") (class "Default")
      (node (ref "U3") (pin "56") (pinfunction "PB4/SPI3_MISO_56") (pintype "passive"))
    )
    (net (code "78") (name "unconnected-(U3-PB5{slash}SPI3_MOSI{slash}ETH_MII_PPS_OUT{slash}ETH_RMII_PPS_OUT-Pad57)") (class "Default")
      (node (ref "U3") (pin "57") (pinfunction "PB5/SPI3_MOSI/ETH_MII_PPS_OUT/ETH_RMII_PPS_OUT_57") (pintype "passive"))
    )
    (net (code "79") (name "unconnected-(U3-PB9{slash}TIM4_CH4-Pad62)") (class "Default")
      (node (ref "U3") (pin "62") (pinfunction "PB9/TIM4_CH4_62") (pintype "passive"))
    )
    (net (code "80") (name "unconnected-(U3-PB10{slash}I2C2_SCL{slash}U3_TX{slash}ETH_MII_RX_ER-Pad29)") (class "Default")
      (node (ref "U3") (pin "29") (pinfunction "PB10/I2C2_SCL/U3_TX/ETH_MII_RX_ER_29") (pintype "passive"))
    )
    (net (code "81") (name "unconnected-(U3-PB14{slash}SPI2_MISO{slash}TIM1_CH2N-Pad35)") (class "Default")
      (node (ref "U3") (pin "35") (pinfunction "PB14/SPI2_MISO/TIM1_CH2N_35") (pintype "passive"))
    )
    (net (code "82") (name "unconnected-(U3-PB15{slash}SPI2_MOSI{slash}TIM1_CH3N-Pad36)") (class "Default")
      (node (ref "U3") (pin "36") (pinfunction "PB15/SPI2_MOSI/TIM1_CH3N_36") (pintype "passive"))
    )
    (net (code "83") (name "unconnected-(U3-PC2{slash}ADC12_IN12{slash}ETH_MII_TXD2-Pad10)") (class "Default")
      (node (ref "U3") (pin "10") (pinfunction "PC2/ADC12_IN12/ETH_MII_TXD2_10") (pintype "passive"))
    )
    (net (code "84") (name "unconnected-(U3-PC3{slash}ADC12_IN13{slash}ETH_MII_TX_CLK-Pad11)") (class "Default")
      (node (ref "U3") (pin "11") (pinfunction "PC3/ADC12_IN13/ETH_MII_TX_CLK_11") (pintype "passive"))
    )
    (net (code "85") (name "unconnected-(U3-PC6-Pad37)") (class "Default")
      (node (ref "U3") (pin "37") (pinfunction "PC6_37") (pintype "passive"))
    )
    (net (code "86") (name "unconnected-(U3-PC7-Pad38)") (class "Default")
      (node (ref "U3") (pin "38") (pinfunction "PC7_38") (pintype "passive"))
    )
    (net (code "87") (name "unconnected-(U3-PC8-Pad39)") (class "Default")
      (node (ref "U3") (pin "39") (pinfunction "PC8_39") (pintype "passive"))
    )
    (net (code "88") (name "unconnected-(U3-PC9-Pad40)") (class "Default")
      (node (ref "U3") (pin "40") (pinfunction "PC9_40") (pintype "passive"))
    )
    (net (code "89") (name "unconnected-(U3-PC13{slash}TAMPER-RTC-Pad2)") (class "Default")
      (node (ref "U3") (pin "2") (pinfunction "PC13/TAMPER-RTC_2") (pintype "passive"))
    )
    (net (code "90") (name "unconnected-(U3-PD2{slash}U5_RX-Pad54)") (class "Default")
      (node (ref "U3") (pin "54") (pinfunction "PD2/U5_RX_54") (pintype "passive"))
    )
  )
)
